# untitled.net
KiCad netlist of a schematic drawn in EAGLE
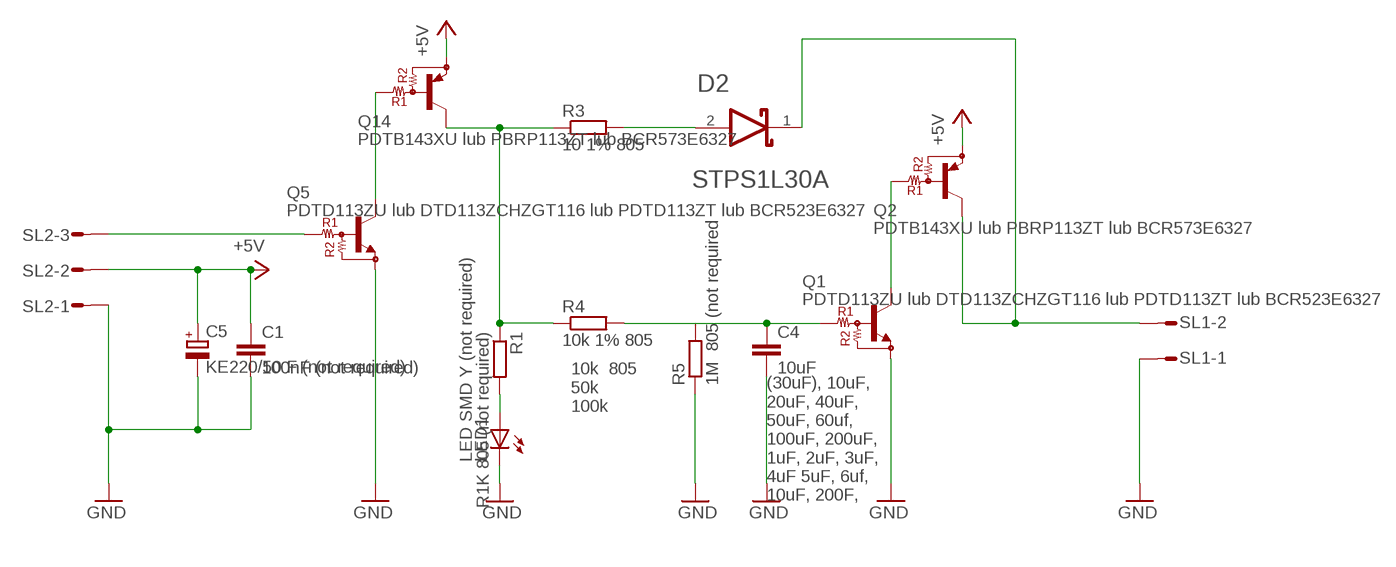
[diagram p0: schematic, sheet 1]

(export (version "E")
  (design (tool "Eeschema 10.0.6"))
  (components
    (comp (ref "C1")
      (value "100nF (not required)")
      (footprint "eagle-import:C0805")
      (libsource (lib "eagle-import") (part "C-EUC0805"))
    )
    (comp (ref "C4")
      (value "10uF")
      (footprint "eagle-import:C0805")
      (libsource (lib "eagle-import") (part "C-EUC0805"))
    )
    (comp (ref "C5")
      (value "KE220/50 F (not required)")
      (footprint "eagle-import:PANASONIC_G")
      (libsource (lib "eagle-import") (part "CPOL-EUG"))
    )
    (comp (ref "D2")
      (value "MBR0530T1G, STPS1L30A lub STPS1L30U")
      (footprint "eagle-import:STMICROELECTRONICS_STPS1L30A_0")
      (fields
        (field (name "DIGIKEY_PART_NUMBER") "497-6577-1-ND")
        (field (name "MF") "STMicroelectronics")
        (field (name "MOUSER_PART_NUMBER") "511-STPS1L30A")
      )
      (libsource (lib "eagle-import") (part "STMICROELECTRONICS_STPS1L30ASTMICROELECTRONICS_STPS1L30A_0_0"))
    )
    (comp (ref "LED1")
      (value "LED SMD Y (not required)")
      (footprint "eagle-import:CHIP-LED0805")
      (libsource (lib "eagle-import") (part "LEDCHIP-LED0805"))
    )
    (comp (ref "Q1")
      (value "PDTD113ZU lub DTD113ZCHZGT116 lub PDTD113ZT lub BCR523E6327")
      (footprint "eagle-import:SOT-23")
      (libsource (lib "eagle-import") (part "PDTD113ZU"))
    )
    (comp (ref "Q2")
      (value "PDTB143XU lub PBRP113ZT lub BCR573E6327")
      (footprint "eagle-import:SOT-23")
      (libsource (lib "eagle-import") (part "PDTB143XU"))
    )
    (comp (ref "Q5")
      (value "PDTD113ZU lub DTD113ZCHZGT116 lub PDTD113ZT lub BCR523E6327")
      (footprint "eagle-import:SOT-23")
      (libsource (lib "eagle-import") (part "PDTD113ZU"))
    )
    (comp (ref "Q14")
      (value "PDTB143XU lub PBRP113ZT lub BCR573E6327")
      (footprint "eagle-import:SOT-23")
      (libsource (lib "eagle-import") (part "PDTB143XU"))
    )
    (comp (ref "R1")
      (value "R1K 805 (not required)")
      (footprint "eagle-import:R0805")
      (libsource (lib "eagle-import") (part "R-EU_R0805"))
    )
    (comp (ref "R3")
      (value "10 1% 805")
      (footprint "eagle-import:M0805")
      (libsource (lib "eagle-import") (part "R-EU_M0805"))
    )
    (comp (ref "R4")
      (value "10k 1% 805")
      (footprint "eagle-import:M0805")
      (libsource (lib "eagle-import") (part "R-EU_M0805"))
    )
    (comp (ref "R5")
      (value "1M 805 (not required")
      (footprint "eagle-import:M0805")
      (libsource (lib "eagle-import") (part "R-EU_M0805"))
    )
    (comp (ref "SL1")
      (value "M02S")
      (footprint "eagle-import:02P")
      (libsource (lib "eagle-import") (part "M02S"))
    )
    (comp (ref "SL2")
      (value "M03S")
      (footprint "eagle-import:03P")
      (libsource (lib "eagle-import") (part "M03S"))
    )
  )
  (nets
    (net (code "1") (name "+5V") (class "Default")
      (node (ref "C1") (pin "1") (pinfunction "1_1") (pintype "passive"))
      (node (ref "C5") (pin "+") (pinfunction "+_+") (pintype "passive"))
      (node (ref "Q14") (pin "2") (pinfunction "E_2") (pintype "passive"))
      (node (ref "Q2") (pin "2") (pinfunction "E_2") (pintype "passive"))
      (node (ref "SL2") (pin "2") (pinfunction "S_2") (pintype "passive"))
    )
    (net (code "2") (name "GND") (class "Default")
      (node (ref "C1") (pin "2") (pinfunction "2_2") (pintype "passive"))
      (node (ref "C4") (pin "2") (pinfunction "2_2") (pintype "passive"))
      (node (ref "C5") (pin "-") (pinfunction "-_-") (pintype "passive"))
      (node (ref "LED1") (pin "C") (pinfunction "C_C") (pintype "passive"))
      (node (ref "Q1") (pin "2") (pinfunction "E_2") (pintype "passive"))
      (node (ref "Q5") (pin "2") (pinfunction "E_2") (pintype "passive"))
      (node (ref "R5") (pin "1") (pinfunction "1_1") (pintype "passive"))
      (node (ref "SL1") (pin "1") (pinfunction "S_1") (pintype "passive"))
      (node (ref "SL2") (pin "1") (pinfunction "S_1") (pintype "passive"))
    )
    (net (code "3") (name "Net-(D2-ANODE)") (class "Default")
      (node (ref "D2") (pin "2") (pinfunction "ANODE_2") (pintype "bidirectional"))
      (node (ref "R3") (pin "2") (pinfunction "2_2") (pintype "passive"))
    )
    (net (code "4") (name "Net-(D2-CATHODE)") (class "Default")
      (node (ref "D2") (pin "1") (pinfunction "CATHODE_1") (pintype "bidirectional"))
      (node (ref "Q2") (pin "3") (pinfunction "C_3") (pintype "passive"))
      (node (ref "SL1") (pin "2") (pinfunction "S_2") (pintype "passive"))
    )
    (net (code "5") (name "Net-(LED1-PadA)") (class "Default")
      (node (ref "LED1") (pin "A") (pinfunction "A_A") (pintype "passive"))
      (node (ref "R1") (pin "2") (pinfunction "2_2") (pintype "passive"))
    )
    (net (code "6") (name "Net-(Q1-B)") (class "Default")
      (node (ref "C4") (pin "1") (pinfunction "1_1") (pintype "passive"))
      (node (ref "Q1") (pin "1") (pinfunction "B_1") (pintype "passive"))
      (node (ref "R4") (pin "2") (pinfunction "2_2") (pintype "passive"))
      (node (ref "R5") (pin "2") (pinfunction "2_2") (pintype "passive"))
    )
    (net (code "7") (name "Net-(Q1-C)") (class "Default")
      (node (ref "Q1") (pin "3") (pinfunction "C_3") (pintype "passive"))
      (node (ref "Q2") (pin "1") (pinfunction "B_1") (pintype "passive"))
    )
    (net (code "8") (name "Net-(Q5-B)") (class "Default")
      (node (ref "Q5") (pin "1") (pinfunction "B_1") (pintype "passive"))
      (node (ref "SL2") (pin "3") (pinfunction "S_3") (pintype "passive"))
    )
    (net (code "9") (name "Net-(Q14-B)") (class "Default")
      (node (ref "Q14") (pin "1") (pinfunction "B_1") (pintype "passive"))
      (node (ref "Q5") (pin "3") (pinfunction "C_3") (pintype "passive"))
    )
    (net (code "10") (name "Net-(Q14-C)") (class "Default")
      (node (ref "Q14") (pin "3") (pinfunction "C_3") (pintype "passive"))
      (node (ref "R1") (pin "1") (pinfunction "1_1") (pintype "passive"))
      (node (ref "R3") (pin "1") (pinfunction "1_1") (pintype "passive"))
      (node (ref "R4") (pin "1") (pinfunction "1_1") (pintype "passive"))
    )
  )
)
